# Bras_droit.net
KiCad netlist of a schematic drawn in EasyEDA
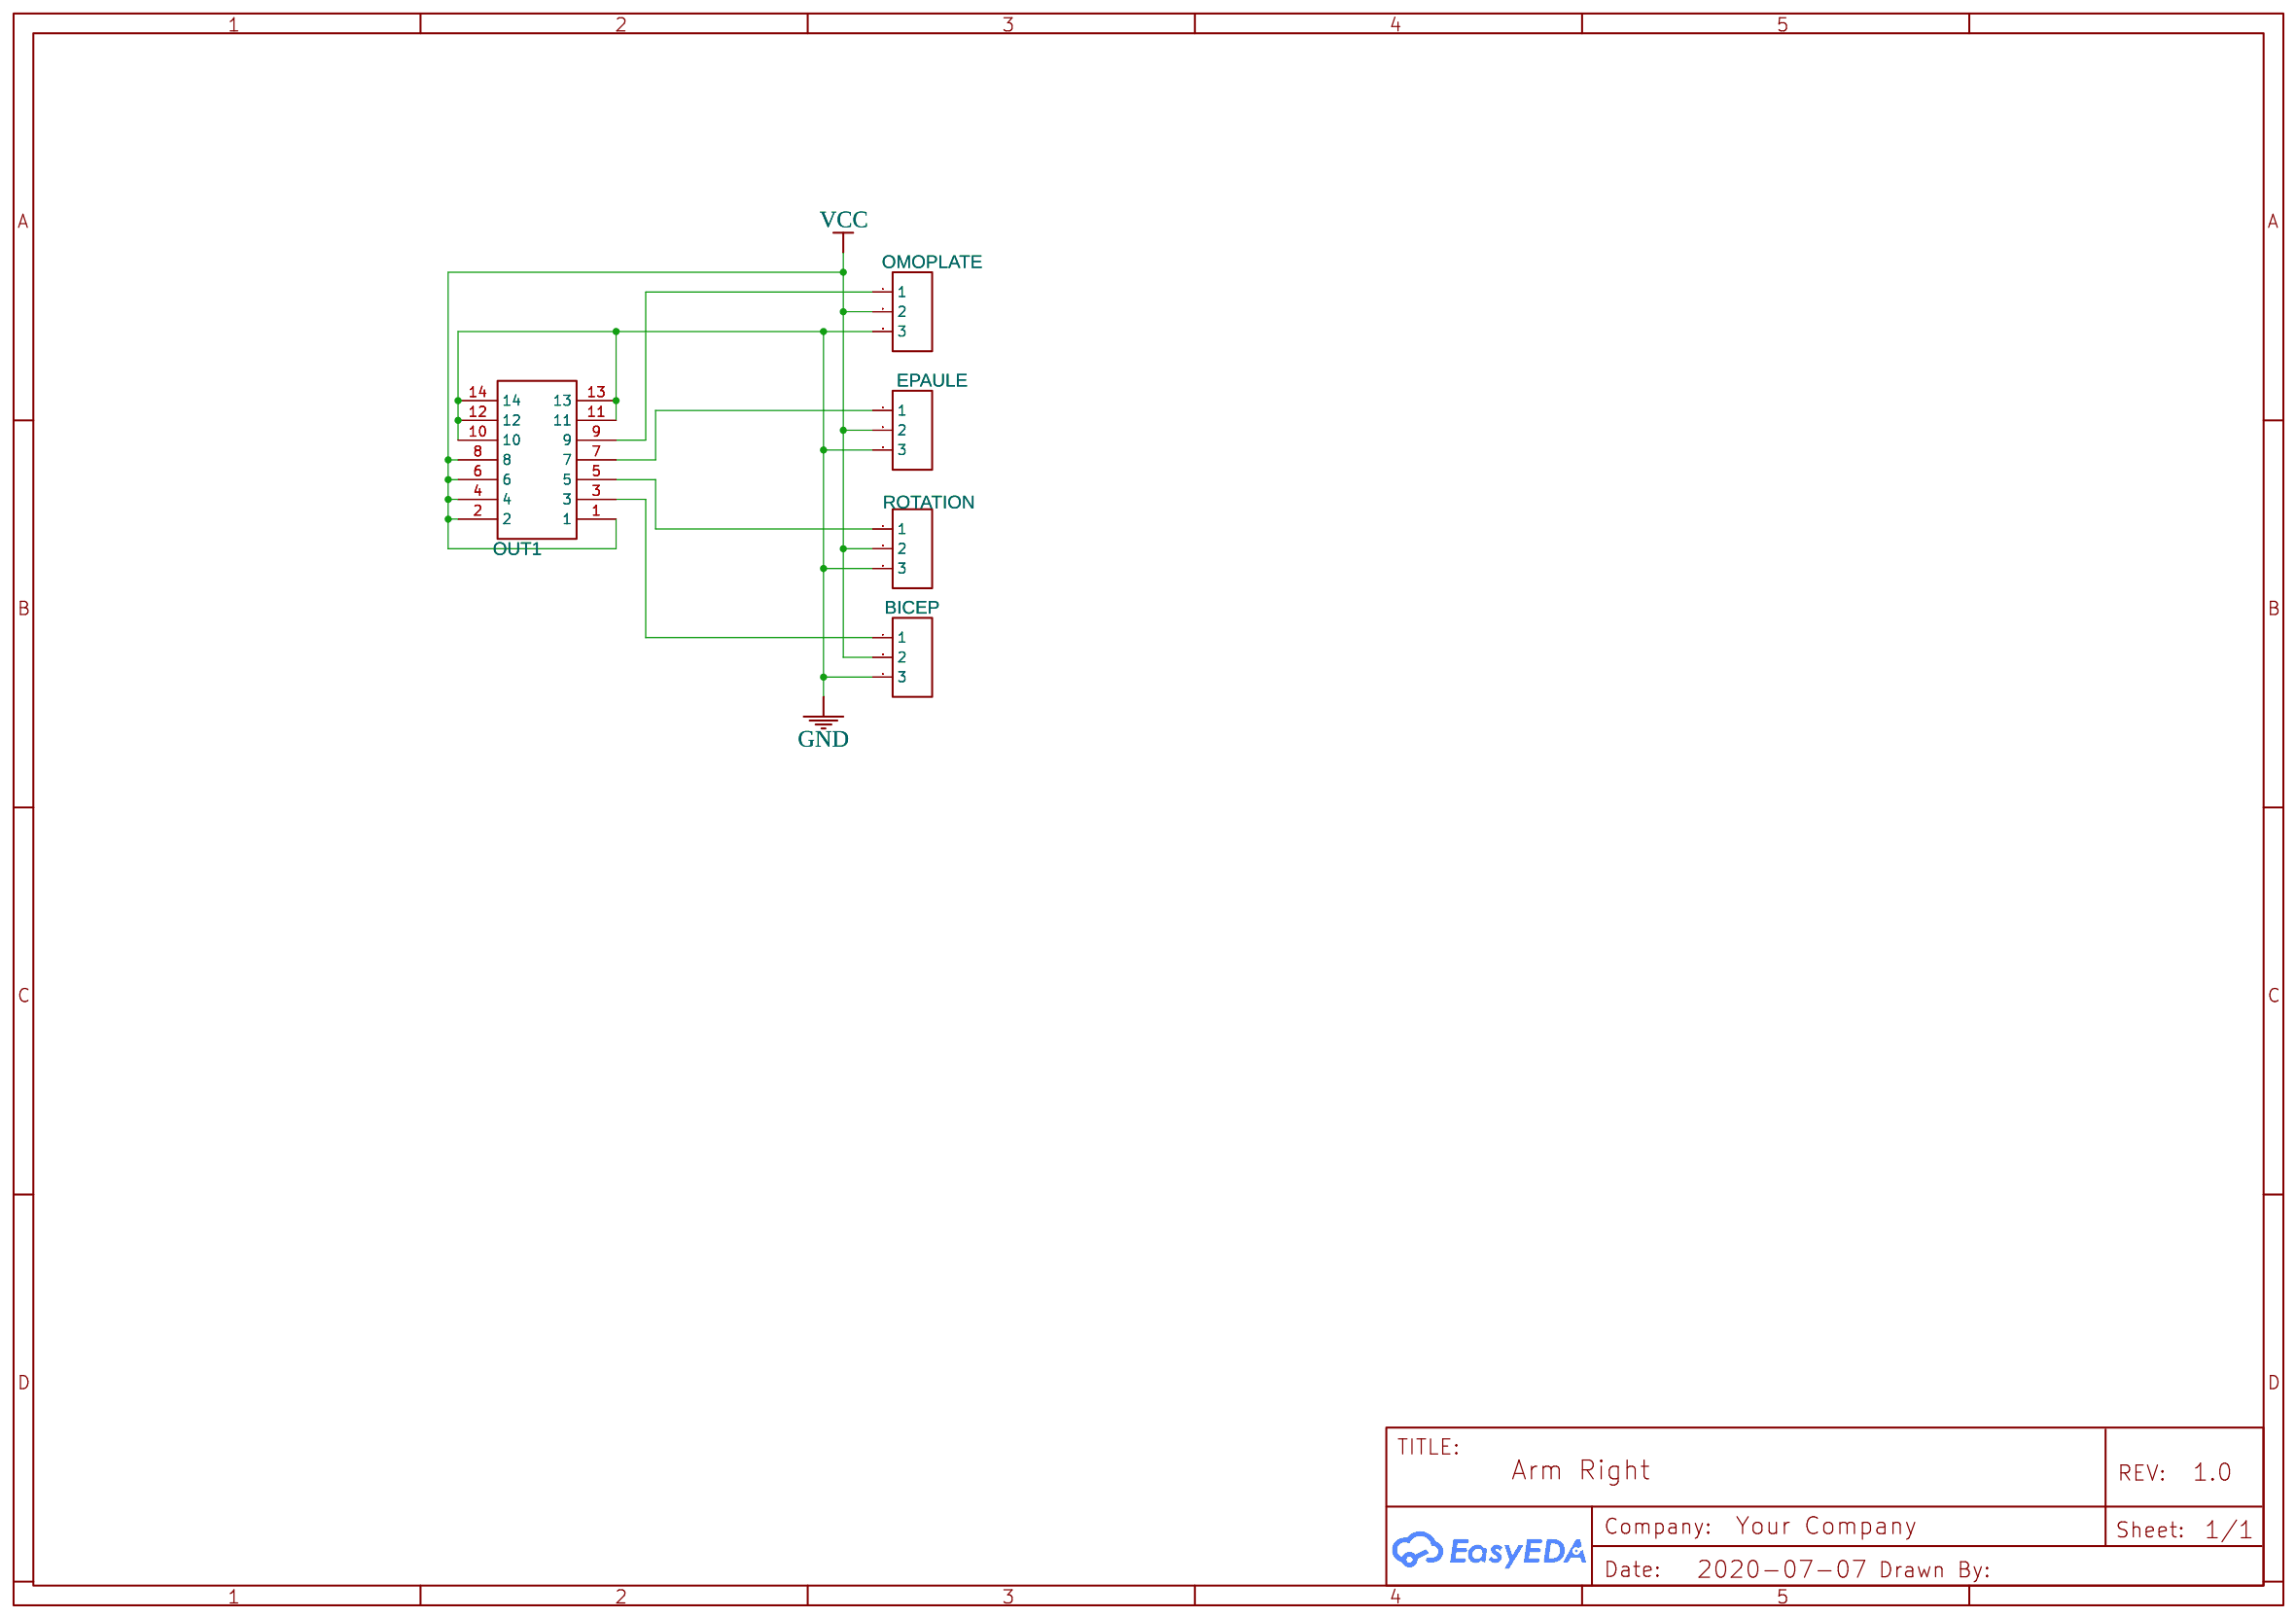
[diagram p0: schematic sheet]

(export (version "E")
  (design (tool "Eeschema 10.0.6"))
  (components
    (comp (ref "BICEP")
      (value "1")
      (fields
        (field (name "BOM_Manufacturer Part") "Header2.54mm 1*3P")
        (field (name "BOM_Supplier Part") "C49257")
      )
      (libsource (lib "") (part "Header-Male-2.54_1x3_3"))
    )
    (comp (ref "EPAULE")
      (value "1")
      (fields
        (field (name "BOM_Manufacturer Part") "Header2.54mm 1*3P")
        (field (name "BOM_Supplier Part") "C49257")
      )
      (libsource (lib "") (part "Header-Male-2.54_1x3"))
    )
    (comp (ref "OMOPLATE")
      (value "1")
      (fields
        (field (name "BOM_Manufacturer Part") "Header2.54mm 1*3P")
        (field (name "BOM_Supplier Part") "C49257")
      )
      (libsource (lib "") (part "Header-Male-2.54_1x3_2"))
    )
    (comp (ref "OUT1")
      (value "Horn connector/2.0mm2*7P")
      (fields
        (field (name "BOM_Manufacturer Part") "Horn connector/2.0mm2*7P直简牛")
        (field (name "BOM_Supplier Part") "C29428")
      )
      (libsource (lib "") (part "Horn connector/2.0mm2*7P"))
    )
    (comp (ref "ROTATION")
      (value "1")
      (fields
        (field (name "BOM_Manufacturer Part") "Header2.54mm 1*3P")
        (field (name "BOM_Supplier Part") "C49257")
      )
      (libsource (lib "") (part "Header-Male-2.54_1x3_1"))
    )
  )
  (nets
    (net (code "1") (name "GND") (class "Default")
      (node (ref "BICEP") (pin "3") (pinfunction "3_3") (pintype "input"))
      (node (ref "EPAULE") (pin "3") (pinfunction "3_3") (pintype "input"))
      (node (ref "OMOPLATE") (pin "3") (pinfunction "3_3") (pintype "input"))
      (node (ref "OUT1") (pin "10") (pinfunction "10_10") (pintype "unspecified"))
      (node (ref "OUT1") (pin "11") (pinfunction "11_11") (pintype "unspecified"))
      (node (ref "OUT1") (pin "12") (pinfunction "12_12") (pintype "unspecified"))
      (node (ref "OUT1") (pin "13") (pinfunction "13_13") (pintype "unspecified"))
      (node (ref "OUT1") (pin "14") (pinfunction "14_14") (pintype "unspecified"))
      (node (ref "ROTATION") (pin "3") (pinfunction "3_3") (pintype "input"))
    )
    (net (code "2") (name "Net-(BICEP-Pad1)") (class "Default")
      (node (ref "BICEP") (pin "1") (pinfunction "1_1") (pintype "input"))
      (node (ref "OUT1") (pin "3") (pinfunction "3_3") (pintype "unspecified"))
    )
    (net (code "3") (name "Net-(EPAULE-Pad1)") (class "Default")
      (node (ref "EPAULE") (pin "1") (pinfunction "1_1") (pintype "input"))
      (node (ref "OUT1") (pin "7") (pinfunction "7_7") (pintype "unspecified"))
    )
    (net (code "4") (name "Net-(OMOPLATE-Pad1)") (class "Default")
      (node (ref "OMOPLATE") (pin "1") (pinfunction "1_1") (pintype "input"))
      (node (ref "OUT1") (pin "9") (pinfunction "9_9") (pintype "unspecified"))
    )
    (net (code "5") (name "Net-(OUT1-Pad5)") (class "Default")
      (node (ref "OUT1") (pin "5") (pinfunction "5_5") (pintype "unspecified"))
      (node (ref "ROTATION") (pin "1") (pinfunction "1_1") (pintype "input"))
    )
    (net (code "6") (name "VCC") (class "Default")
      (node (ref "BICEP") (pin "2") (pinfunction "2_2") (pintype "input"))
      (node (ref "EPAULE") (pin "2") (pinfunction "2_2") (pintype "input"))
      (node (ref "OMOPLATE") (pin "2") (pinfunction "2_2") (pintype "input"))
      (node (ref "OUT1") (pin "1") (pinfunction "1_1") (pintype "unspecified"))
      (node (ref "OUT1") (pin "2") (pinfunction "2_2") (pintype "unspecified"))
      (node (ref "OUT1") (pin "4") (pinfunction "4_4") (pintype "unspecified"))
      (node (ref "OUT1") (pin "6") (pinfunction "6_6") (pintype "unspecified"))
      (node (ref "OUT1") (pin "8") (pinfunction "8_8") (pintype "unspecified"))
      (node (ref "ROTATION") (pin "2") (pinfunction "2_2") (pintype "input"))
    )
  )
)
